# MT48LC4M16A2.net
KiCad netlist of a schematic drawn in Altium Designer
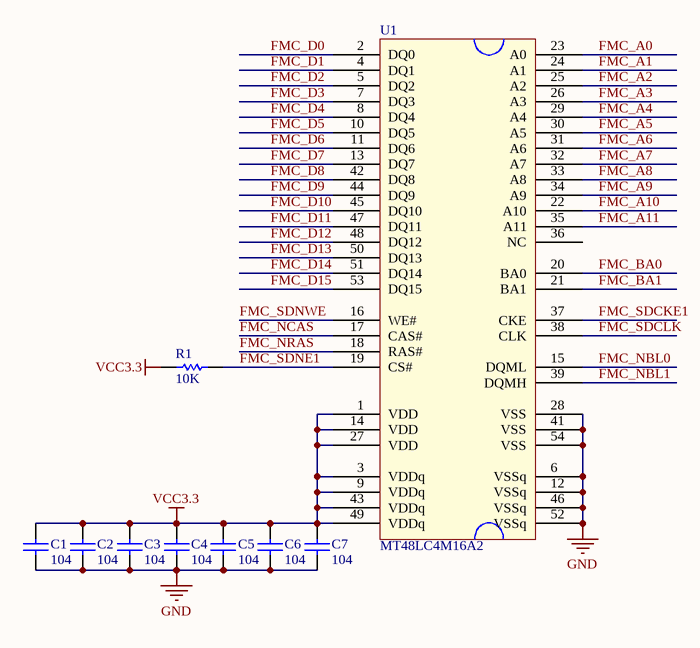
[diagram p0: MT48LC4M16A2.SchDoc]

(export (version "E")
  (design (tool "Eeschema 10.0.6"))
  (components
    (comp (ref "C1")
      (value "104")
      (footprint "0603C")
      (description "电容")
      (libsource (lib "常用元件") (part "CAP-0603"))
    )
    (comp (ref "C2")
      (value "104")
      (footprint "0603C")
      (description "电容")
      (libsource (lib "常用元件") (part "CAP-0603"))
    )
    (comp (ref "C3")
      (value "104")
      (footprint "0603C")
      (description "电容")
      (libsource (lib "常用元件") (part "CAP-0603"))
    )
    (comp (ref "C4")
      (value "104")
      (footprint "0603C")
      (description "电容")
      (libsource (lib "常用元件") (part "CAP-0603"))
    )
    (comp (ref "C5")
      (value "104")
      (footprint "0603C")
      (description "电容")
      (libsource (lib "常用元件") (part "CAP-0603"))
    )
    (comp (ref "C6")
      (value "104")
      (footprint "0603C")
      (description "电容")
      (libsource (lib "常用元件") (part "CAP-0603"))
    )
    (comp (ref "C7")
      (value "104")
      (footprint "0603C")
      (description "电容")
      (libsource (lib "常用元件") (part "CAP-0603"))
    )
    (comp (ref "R1")
      (value "10K")
      (footprint "0603R")
      (description "Resistance")
      (libsource (lib "常用元件") (part "RES-0603"))
    )
    (comp (ref "U1")
      (value "MT48LC4M16A2")
      (footprint "TSOP-54")
      (description "16位64Mb SDRAM")
      (libsource (lib "常用元件") (part "MT48LC4M16A2"))
    )
  )
  (nets
    (net (code "1") (name "/FMC_A0") (class "Default")
      (node (ref "U1") (pin "23") (pinfunction "A0_23") (pintype "passive"))
    )
    (net (code "2") (name "/FMC_A1") (class "Default")
      (node (ref "U1") (pin "24") (pinfunction "A1_24") (pintype "passive"))
    )
    (net (code "3") (name "/FMC_A2") (class "Default")
      (node (ref "U1") (pin "25") (pinfunction "A2_25") (pintype "passive"))
    )
    (net (code "4") (name "/FMC_A3") (class "Default")
      (node (ref "U1") (pin "26") (pinfunction "A3_26") (pintype "passive"))
    )
    (net (code "5") (name "/FMC_A4") (class "Default")
      (node (ref "U1") (pin "29") (pinfunction "A4_29") (pintype "passive"))
    )
    (net (code "6") (name "/FMC_A5") (class "Default")
      (node (ref "U1") (pin "30") (pinfunction "A5_30") (pintype "passive"))
    )
    (net (code "7") (name "/FMC_A6") (class "Default")
      (node (ref "U1") (pin "31") (pinfunction "A6_31") (pintype "passive"))
    )
    (net (code "8") (name "/FMC_A7") (class "Default")
      (node (ref "U1") (pin "32") (pinfunction "A7_32") (pintype "passive"))
    )
    (net (code "9") (name "/FMC_A8") (class "Default")
      (node (ref "U1") (pin "33") (pinfunction "A8_33") (pintype "passive"))
    )
    (net (code "10") (name "/FMC_A9") (class "Default")
      (node (ref "U1") (pin "34") (pinfunction "A9_34") (pintype "passive"))
    )
    (net (code "11") (name "/FMC_A10") (class "Default")
      (node (ref "U1") (pin "22") (pinfunction "A10_22") (pintype "passive"))
    )
    (net (code "12") (name "/FMC_A11") (class "Default")
      (node (ref "U1") (pin "35") (pinfunction "A11_35") (pintype "passive"))
    )
    (net (code "13") (name "/FMC_BA0") (class "Default")
      (node (ref "U1") (pin "20") (pinfunction "BA0_20") (pintype "passive"))
    )
    (net (code "14") (name "/FMC_BA1") (class "Default")
      (node (ref "U1") (pin "21") (pinfunction "BA1_21") (pintype "passive"))
    )
    (net (code "15") (name "/FMC_D0") (class "Default")
      (node (ref "U1") (pin "2") (pinfunction "DQ0_2") (pintype "passive"))
    )
    (net (code "16") (name "/FMC_D1") (class "Default")
      (node (ref "U1") (pin "4") (pinfunction "DQ1_4") (pintype "passive"))
    )
    (net (code "17") (name "/FMC_D2") (class "Default")
      (node (ref "U1") (pin "5") (pinfunction "DQ2_5") (pintype "passive"))
    )
    (net (code "18") (name "/FMC_D3") (class "Default")
      (node (ref "U1") (pin "7") (pinfunction "DQ3_7") (pintype "passive"))
    )
    (net (code "19") (name "/FMC_D4") (class "Default")
      (node (ref "U1") (pin "8") (pinfunction "DQ4_8") (pintype "passive"))
    )
    (net (code "20") (name "/FMC_D5") (class "Default")
      (node (ref "U1") (pin "10") (pinfunction "DQ5_10") (pintype "passive"))
    )
    (net (code "21") (name "/FMC_D6") (class "Default")
      (node (ref "U1") (pin "11") (pinfunction "DQ6_11") (pintype "passive"))
    )
    (net (code "22") (name "/FMC_D7") (class "Default")
      (node (ref "U1") (pin "13") (pinfunction "DQ7_13") (pintype "passive"))
    )
    (net (code "23") (name "/FMC_D8") (class "Default")
      (node (ref "U1") (pin "42") (pinfunction "DQ8_42") (pintype "passive"))
    )
    (net (code "24") (name "/FMC_D9") (class "Default")
      (node (ref "U1") (pin "44") (pinfunction "DQ9_44") (pintype "passive"))
    )
    (net (code "25") (name "/FMC_D10") (class "Default")
      (node (ref "U1") (pin "45") (pinfunction "DQ10_45") (pintype "passive"))
    )
    (net (code "26") (name "/FMC_D11") (class "Default")
      (node (ref "U1") (pin "47") (pinfunction "DQ11_47") (pintype "passive"))
    )
    (net (code "27") (name "/FMC_D12") (class "Default")
      (node (ref "U1") (pin "48") (pinfunction "DQ12_48") (pintype "passive"))
    )
    (net (code "28") (name "/FMC_D13") (class "Default")
      (node (ref "U1") (pin "50") (pinfunction "DQ13_50") (pintype "passive"))
    )
    (net (code "29") (name "/FMC_D14") (class "Default")
      (node (ref "U1") (pin "51") (pinfunction "DQ14_51") (pintype "passive"))
    )
    (net (code "30") (name "/FMC_D15") (class "Default")
      (node (ref "U1") (pin "53") (pinfunction "DQ15_53") (pintype "passive"))
    )
    (net (code "31") (name "/FMC_NBL0") (class "Default")
      (node (ref "U1") (pin "15") (pinfunction "DQML_15") (pintype "passive"))
    )
    (net (code "32") (name "/FMC_NBL1") (class "Default")
      (node (ref "U1") (pin "39") (pinfunction "DQMH_39") (pintype "passive"))
    )
    (net (code "33") (name "/FMC_NCAS") (class "Default")
      (node (ref "U1") (pin "17") (pinfunction "CAS#_17") (pintype "passive"))
    )
    (net (code "34") (name "/FMC_NRAS") (class "Default")
      (node (ref "U1") (pin "18") (pinfunction "RAS#_18") (pintype "passive"))
    )
    (net (code "35") (name "/FMC_SDCKE1") (class "Default")
      (node (ref "U1") (pin "37") (pinfunction "CKE_37") (pintype "passive"))
    )
    (net (code "36") (name "/FMC_SDCLK") (class "Default")
      (node (ref "U1") (pin "38") (pinfunction "CLK_38") (pintype "passive"))
    )
    (net (code "37") (name "/FMC_SDNE1") (class "Default")
      (node (ref "R1") (pin "2") (pinfunction "2_2") (pintype "passive"))
      (node (ref "U1") (pin "19") (pinfunction "CS#_19") (pintype "passive"))
    )
    (net (code "38") (name "/FMC_SDNWE") (class "Default")
      (node (ref "U1") (pin "16") (pinfunction "WE#_16") (pintype "passive"))
    )
    (net (code "39") (name "GND") (class "Default")
      (node (ref "C1") (pin "1") (pinfunction "1_1") (pintype "passive"))
      (node (ref "C2") (pin "1") (pinfunction "1_1") (pintype "passive"))
      (node (ref "C3") (pin "1") (pinfunction "1_1") (pintype "passive"))
      (node (ref "C4") (pin "1") (pinfunction "1_1") (pintype "passive"))
      (node (ref "C5") (pin "1") (pinfunction "1_1") (pintype "passive"))
      (node (ref "C6") (pin "1") (pinfunction "1_1") (pintype "passive"))
      (node (ref "C7") (pin "1") (pinfunction "1_1") (pintype "passive"))
      (node (ref "U1") (pin "12") (pinfunction "VSSq_12") (pintype "passive"))
      (node (ref "U1") (pin "28") (pinfunction "VSS_28") (pintype "passive"))
      (node (ref "U1") (pin "41") (pinfunction "VSS_41") (pintype "passive"))
      (node (ref "U1") (pin "46") (pinfunction "VSSq_46") (pintype "passive"))
      (node (ref "U1") (pin "52") (pinfunction "VSSq_52") (pintype "passive"))
      (node (ref "U1") (pin "54") (pinfunction "VSS_54") (pintype "passive"))
      (node (ref "U1") (pin "6") (pinfunction "VSSq_6") (pintype "passive"))
    )
    (net (code "40") (name "VCC3.3") (class "Default")
      (node (ref "C1") (pin "2") (pinfunction "2_2") (pintype "passive"))
      (node (ref "C2") (pin "2") (pinfunction "2_2") (pintype "passive"))
      (node (ref "C3") (pin "2") (pinfunction "2_2") (pintype "passive"))
      (node (ref "C4") (pin "2") (pinfunction "2_2") (pintype "passive"))
      (node (ref "C5") (pin "2") (pinfunction "2_2") (pintype "passive"))
      (node (ref "C6") (pin "2") (pinfunction "2_2") (pintype "passive"))
      (node (ref "C7") (pin "2") (pinfunction "2_2") (pintype "passive"))
      (node (ref "R1") (pin "1") (pinfunction "1_1") (pintype "passive"))
      (node (ref "U1") (pin "1") (pinfunction "VDD_1") (pintype "passive"))
      (node (ref "U1") (pin "14") (pinfunction "VDD_14") (pintype "passive"))
      (node (ref "U1") (pin "27") (pinfunction "VDD_27") (pintype "passive"))
      (node (ref "U1") (pin "3") (pinfunction "VDDq_3") (pintype "passive"))
      (node (ref "U1") (pin "43") (pinfunction "VDDq_43") (pintype "passive"))
      (node (ref "U1") (pin "49") (pinfunction "VDDq_49") (pintype "passive"))
      (node (ref "U1") (pin "9") (pinfunction "VDDq_9") (pintype "passive"))
    )
    (net (code "41") (name "unconnected-(U1-NC-Pad36)") (class "Default")
      (node (ref "U1") (pin "36") (pinfunction "NC_36") (pintype "passive"))
    )
    (net (code "42") (name "unconnected-(U1-NC-Pad40)") (class "Default")
      (node (ref "U1") (pin "40") (pinfunction "NC_40") (pintype "passive"))
    )
  )
)
